# SwitchMatrix.net
KiCad netlist of a schematic drawn in Altium Designer
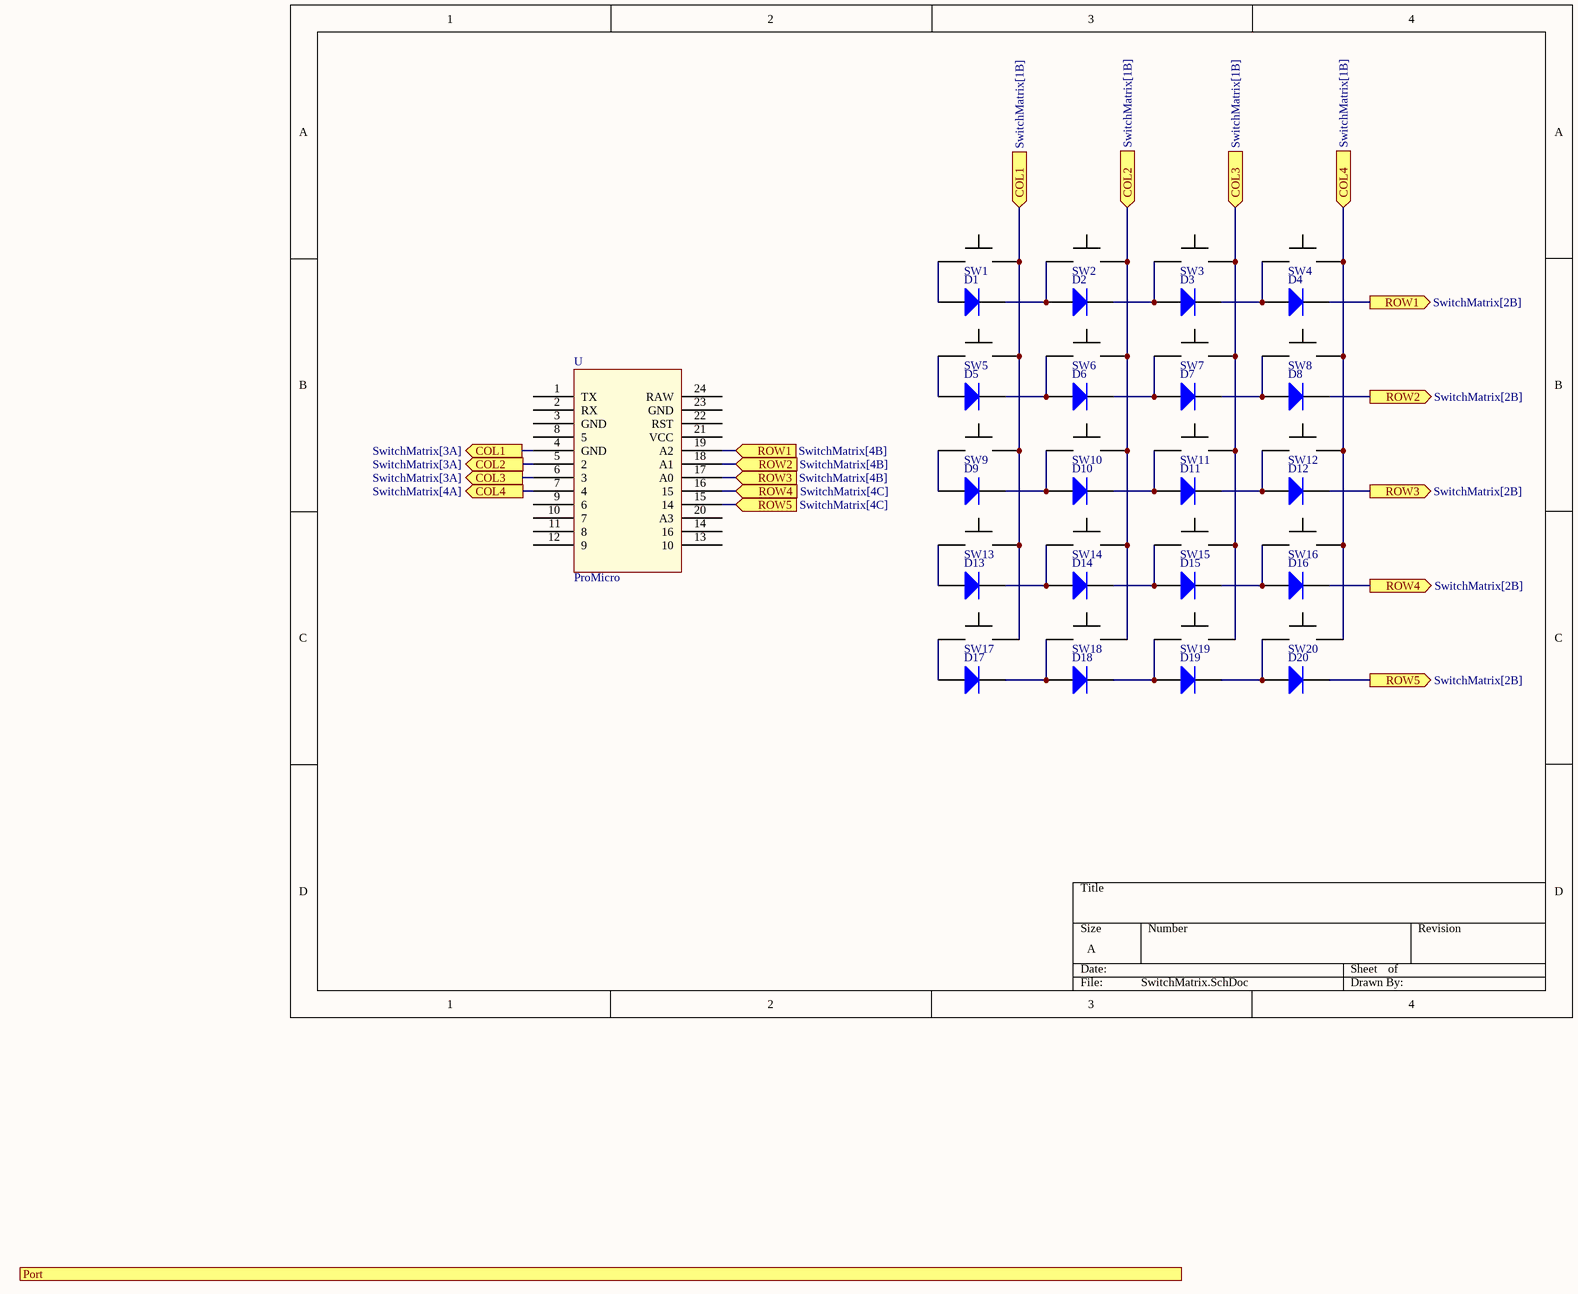
[diagram p0: SwitchMatrix.SchDoc]

(export (version "E")
  (design (tool "Eeschema 10.0.6"))
  (components
    (comp (ref "D1") (value "Diode") (libsource (lib "Simulation Generic Components") (part "Diode")))
    (comp (ref "D2") (value "Diode") (libsource (lib "Simulation Generic Components") (part "Diode")))
    (comp (ref "D3") (value "Diode") (libsource (lib "Simulation Generic Components") (part "Diode")))
    (comp (ref "D4") (value "Diode") (libsource (lib "Simulation Generic Components") (part "Diode")))
    (comp (ref "D5") (value "Diode") (libsource (lib "Simulation Generic Components") (part "Diode")))
    (comp (ref "D6") (value "Diode") (libsource (lib "Simulation Generic Components") (part "Diode")))
    (comp (ref "D7") (value "Diode") (libsource (lib "Simulation Generic Components") (part "Diode")))
    (comp (ref "D8") (value "Diode") (libsource (lib "Simulation Generic Components") (part "Diode")))
    (comp (ref "D9") (value "Diode") (libsource (lib "Simulation Generic Components") (part "Diode")))
    (comp (ref "D10") (value "Diode") (libsource (lib "Simulation Generic Components") (part "Diode")))
    (comp (ref "D11") (value "Diode") (libsource (lib "Simulation Generic Components") (part "Diode")))
    (comp (ref "D12") (value "Diode") (libsource (lib "Simulation Generic Components") (part "Diode")))
    (comp (ref "D13") (value "Diode") (libsource (lib "Simulation Generic Components") (part "Diode")))
    (comp (ref "D14") (value "Diode") (libsource (lib "Simulation Generic Components") (part "Diode")))
    (comp (ref "D15") (value "Diode") (libsource (lib "Simulation Generic Components") (part "Diode")))
    (comp (ref "D16") (value "Diode") (libsource (lib "Simulation Generic Components") (part "Diode")))
    (comp (ref "D17") (value "Diode") (libsource (lib "Simulation Generic Components") (part "Diode")))
    (comp (ref "D18") (value "Diode") (libsource (lib "Simulation Generic Components") (part "Diode")))
    (comp (ref "D19") (value "Diode") (libsource (lib "Simulation Generic Components") (part "Diode")))
    (comp (ref "D20") (value "Diode") (libsource (lib "Simulation Generic Components") (part "Diode")))
    (comp (ref "SW1")
      (value "PG1350 SW")
      (footprint "PG1350")
      (libsource (lib "altium-practice-macropad") (part "PG1350 SW"))
    )
    (comp (ref "SW2")
      (value "PG1350 SW")
      (footprint "PG1350")
      (libsource (lib "altium-practice-macropad") (part "PG1350 SW"))
    )
    (comp (ref "SW3")
      (value "PG1350 SW")
      (footprint "PG1350")
      (libsource (lib "altium-practice-macropad") (part "PG1350 SW"))
    )
    (comp (ref "SW4")
      (value "PG1350 SW")
      (footprint "PG1350")
      (libsource (lib "altium-practice-macropad") (part "PG1350 SW"))
    )
    (comp (ref "SW5")
      (value "PG1350 SW")
      (footprint "PG1350")
      (libsource (lib "altium-practice-macropad") (part "PG1350 SW"))
    )
    (comp (ref "SW6")
      (value "PG1350 SW")
      (footprint "PG1350")
      (libsource (lib "altium-practice-macropad") (part "PG1350 SW"))
    )
    (comp (ref "SW7")
      (value "PG1350 SW")
      (footprint "PG1350")
      (libsource (lib "altium-practice-macropad") (part "PG1350 SW"))
    )
    (comp (ref "SW8")
      (value "PG1350 SW")
      (footprint "PG1350")
      (libsource (lib "altium-practice-macropad") (part "PG1350 SW"))
    )
    (comp (ref "SW9")
      (value "PG1350 SW")
      (footprint "PG1350")
      (libsource (lib "altium-practice-macropad") (part "PG1350 SW"))
    )
    (comp (ref "SW10")
      (value "PG1350 SW")
      (footprint "PG1350")
      (libsource (lib "altium-practice-macropad") (part "PG1350 SW"))
    )
    (comp (ref "SW11")
      (value "PG1350 SW")
      (footprint "PG1350")
      (libsource (lib "altium-practice-macropad") (part "PG1350 SW"))
    )
    (comp (ref "SW12")
      (value "PG1350 SW")
      (footprint "PG1350")
      (libsource (lib "altium-practice-macropad") (part "PG1350 SW"))
    )
    (comp (ref "SW13")
      (value "PG1350 SW")
      (footprint "PG1350")
      (libsource (lib "altium-practice-macropad") (part "PG1350 SW"))
    )
    (comp (ref "SW14")
      (value "PG1350 SW")
      (footprint "PG1350")
      (libsource (lib "altium-practice-macropad") (part "PG1350 SW"))
    )
    (comp (ref "SW15")
      (value "PG1350 SW")
      (footprint "PG1350")
      (libsource (lib "altium-practice-macropad") (part "PG1350 SW"))
    )
    (comp (ref "SW16")
      (value "PG1350 SW")
      (footprint "PG1350")
      (libsource (lib "altium-practice-macropad") (part "PG1350 SW"))
    )
    (comp (ref "SW17")
      (value "PG1350 SW")
      (footprint "PG1350")
      (libsource (lib "altium-practice-macropad") (part "PG1350 SW"))
    )
    (comp (ref "SW18")
      (value "PG1350 SW")
      (footprint "PG1350")
      (libsource (lib "altium-practice-macropad") (part "PG1350 SW"))
    )
    (comp (ref "SW19")
      (value "PG1350 SW")
      (footprint "PG1350")
      (libsource (lib "altium-practice-macropad") (part "PG1350 SW"))
    )
    (comp (ref "SW20")
      (value "PG1350 SW")
      (footprint "PG1350")
      (libsource (lib "altium-practice-macropad") (part "PG1350 SW"))
    )
    (comp (ref "U")
      (value "ProMicro")
      (footprint "ProMicroHeaders")
      (libsource (lib "altium-practice-macropad") (part "ProMicro"))
    )
  )
  (nets
    (net (code "1") (name "/COL1") (class "Default")
      (node (ref "SW1") (pin "2") (pintype "passive"))
      (node (ref "SW13") (pin "2") (pintype "passive"))
      (node (ref "SW17") (pin "2") (pintype "passive"))
      (node (ref "SW5") (pin "2") (pintype "passive"))
      (node (ref "SW9") (pin "2") (pintype "passive"))
      (node (ref "U") (pin "4") (pinfunction "GND_4") (pintype "power_in"))
    )
    (net (code "2") (name "/COL2") (class "Default")
      (node (ref "SW10") (pin "2") (pintype "passive"))
      (node (ref "SW14") (pin "2") (pintype "passive"))
      (node (ref "SW18") (pin "2") (pintype "passive"))
      (node (ref "SW2") (pin "2") (pintype "passive"))
      (node (ref "SW6") (pin "2") (pintype "passive"))
      (node (ref "U") (pin "5") (pinfunction "2_5") (pintype "power_in"))
    )
    (net (code "3") (name "/COL3") (class "Default")
      (node (ref "SW11") (pin "2") (pintype "passive"))
      (node (ref "SW15") (pin "2") (pintype "passive"))
      (node (ref "SW19") (pin "2") (pintype "passive"))
      (node (ref "SW3") (pin "2") (pintype "passive"))
      (node (ref "SW7") (pin "2") (pintype "passive"))
      (node (ref "U") (pin "6") (pinfunction "3_6") (pintype "power_in"))
    )
    (net (code "4") (name "/COL4") (class "Default")
      (node (ref "SW12") (pin "2") (pintype "passive"))
      (node (ref "SW16") (pin "2") (pintype "passive"))
      (node (ref "SW20") (pin "2") (pintype "passive"))
      (node (ref "SW4") (pin "2") (pintype "passive"))
      (node (ref "SW8") (pin "2") (pintype "passive"))
      (node (ref "U") (pin "7") (pinfunction "4_7") (pintype "power_in"))
    )
    (net (code "6") (name "/ROW1") (class "Default")
      (node (ref "D4") (pin "2") (pinfunction "K_2") (pintype "passive"))
      (node (ref "U") (pin "19") (pinfunction "A2_19") (pintype "power_in"))
    )
    (net (code "7") (name "/ROW2") (class "Default")
      (node (ref "D8") (pin "2") (pinfunction "K_2") (pintype "passive"))
      (node (ref "U") (pin "18") (pinfunction "A1_18") (pintype "power_in"))
    )
    (net (code "8") (name "/ROW3") (class "Default")
      (node (ref "D12") (pin "2") (pinfunction "K_2") (pintype "passive"))
      (node (ref "U") (pin "17") (pinfunction "A0_17") (pintype "power_in"))
    )
    (net (code "9") (name "/ROW4") (class "Default")
      (node (ref "D16") (pin "2") (pinfunction "K_2") (pintype "passive"))
      (node (ref "U") (pin "16") (pinfunction "15_16") (pintype "power_in"))
    )
    (net (code "10") (name "/ROW5") (class "Default")
      (node (ref "D20") (pin "2") (pinfunction "K_2") (pintype "passive"))
      (node (ref "U") (pin "15") (pinfunction "14_15") (pintype "power_in"))
    )
    (net (code "11") (name "Net-(D1-A)") (class "Default")
      (node (ref "D1") (pin "1") (pinfunction "A_1") (pintype "passive"))
      (node (ref "SW1") (pin "1") (pintype "passive"))
    )
    (net (code "12") (name "Net-(D1-K)") (class "Default")
      (node (ref "D1") (pin "2") (pinfunction "K_2") (pintype "passive"))
      (node (ref "D2") (pin "1") (pinfunction "A_1") (pintype "passive"))
      (node (ref "SW2") (pin "1") (pintype "passive"))
    )
    (net (code "13") (name "Net-(D2-K)") (class "Default")
      (node (ref "D2") (pin "2") (pinfunction "K_2") (pintype "passive"))
      (node (ref "D3") (pin "1") (pinfunction "A_1") (pintype "passive"))
      (node (ref "SW3") (pin "1") (pintype "passive"))
    )
    (net (code "14") (name "Net-(D3-K)") (class "Default")
      (node (ref "D3") (pin "2") (pinfunction "K_2") (pintype "passive"))
      (node (ref "D4") (pin "1") (pinfunction "A_1") (pintype "passive"))
      (node (ref "SW4") (pin "1") (pintype "passive"))
    )
    (net (code "15") (name "Net-(D5-A)") (class "Default")
      (node (ref "D5") (pin "1") (pinfunction "A_1") (pintype "passive"))
      (node (ref "SW5") (pin "1") (pintype "passive"))
    )
    (net (code "16") (name "Net-(D5-K)") (class "Default")
      (node (ref "D5") (pin "2") (pinfunction "K_2") (pintype "passive"))
      (node (ref "D6") (pin "1") (pinfunction "A_1") (pintype "passive"))
      (node (ref "SW6") (pin "1") (pintype "passive"))
    )
    (net (code "17") (name "Net-(D6-K)") (class "Default")
      (node (ref "D6") (pin "2") (pinfunction "K_2") (pintype "passive"))
      (node (ref "D7") (pin "1") (pinfunction "A_1") (pintype "passive"))
      (node (ref "SW7") (pin "1") (pintype "passive"))
    )
    (net (code "18") (name "Net-(D7-K)") (class "Default")
      (node (ref "D7") (pin "2") (pinfunction "K_2") (pintype "passive"))
      (node (ref "D8") (pin "1") (pinfunction "A_1") (pintype "passive"))
      (node (ref "SW8") (pin "1") (pintype "passive"))
    )
    (net (code "19") (name "Net-(D9-A)") (class "Default")
      (node (ref "D9") (pin "1") (pinfunction "A_1") (pintype "passive"))
      (node (ref "SW9") (pin "1") (pintype "passive"))
    )
    (net (code "20") (name "Net-(D10-A)") (class "Default")
      (node (ref "D10") (pin "1") (pinfunction "A_1") (pintype "passive"))
      (node (ref "D9") (pin "2") (pinfunction "K_2") (pintype "passive"))
      (node (ref "SW10") (pin "1") (pintype "passive"))
    )
    (net (code "21") (name "Net-(D10-K)") (class "Default")
      (node (ref "D10") (pin "2") (pinfunction "K_2") (pintype "passive"))
      (node (ref "D11") (pin "1") (pinfunction "A_1") (pintype "passive"))
      (node (ref "SW11") (pin "1") (pintype "passive"))
    )
    (net (code "22") (name "Net-(D11-K)") (class "Default")
      (node (ref "D11") (pin "2") (pinfunction "K_2") (pintype "passive"))
      (node (ref "D12") (pin "1") (pinfunction "A_1") (pintype "passive"))
      (node (ref "SW12") (pin "1") (pintype "passive"))
    )
    (net (code "23") (name "Net-(D13-A)") (class "Default")
      (node (ref "D13") (pin "1") (pinfunction "A_1") (pintype "passive"))
      (node (ref "SW13") (pin "1") (pintype "passive"))
    )
    (net (code "24") (name "Net-(D13-K)") (class "Default")
      (node (ref "D13") (pin "2") (pinfunction "K_2") (pintype "passive"))
      (node (ref "D14") (pin "1") (pinfunction "A_1") (pintype "passive"))
      (node (ref "SW14") (pin "1") (pintype "passive"))
    )
    (net (code "25") (name "Net-(D14-K)") (class "Default")
      (node (ref "D14") (pin "2") (pinfunction "K_2") (pintype "passive"))
      (node (ref "D15") (pin "1") (pinfunction "A_1") (pintype "passive"))
      (node (ref "SW15") (pin "1") (pintype "passive"))
    )
    (net (code "26") (name "Net-(D15-K)") (class "Default")
      (node (ref "D15") (pin "2") (pinfunction "K_2") (pintype "passive"))
      (node (ref "D16") (pin "1") (pinfunction "A_1") (pintype "passive"))
      (node (ref "SW16") (pin "1") (pintype "passive"))
    )
    (net (code "27") (name "Net-(D17-A)") (class "Default")
      (node (ref "D17") (pin "1") (pinfunction "A_1") (pintype "passive"))
      (node (ref "SW17") (pin "1") (pintype "passive"))
    )
    (net (code "28") (name "Net-(D17-K)") (class "Default")
      (node (ref "D17") (pin "2") (pinfunction "K_2") (pintype "passive"))
      (node (ref "D18") (pin "1") (pinfunction "A_1") (pintype "passive"))
      (node (ref "SW18") (pin "1") (pintype "passive"))
    )
    (net (code "29") (name "Net-(D18-K)") (class "Default")
      (node (ref "D18") (pin "2") (pinfunction "K_2") (pintype "passive"))
      (node (ref "D19") (pin "1") (pinfunction "A_1") (pintype "passive"))
      (node (ref "SW19") (pin "1") (pintype "passive"))
    )
    (net (code "30") (name "Net-(D19-K)") (class "Default")
      (node (ref "D19") (pin "2") (pinfunction "K_2") (pintype "passive"))
      (node (ref "D20") (pin "1") (pinfunction "A_1") (pintype "passive"))
      (node (ref "SW20") (pin "1") (pintype "passive"))
    )
    (net (code "31") (name "unconnected-(U-5-Pad8)") (class "Default")
      (node (ref "U") (pin "8") (pinfunction "5_8") (pintype "power_in"))
    )
    (net (code "32") (name "unconnected-(U-6-Pad9)") (class "Default")
      (node (ref "U") (pin "9") (pinfunction "6_9") (pintype "power_in"))
    )
    (net (code "33") (name "unconnected-(U-7-Pad10)") (class "Default")
      (node (ref "U") (pin "10") (pinfunction "7_10") (pintype "power_in"))
    )
    (net (code "34") (name "unconnected-(U-8-Pad11)") (class "Default")
      (node (ref "U") (pin "11") (pinfunction "8_11") (pintype "power_in"))
    )
    (net (code "35") (name "unconnected-(U-9-Pad12)") (class "Default")
      (node (ref "U") (pin "12") (pinfunction "9_12") (pintype "power_in"))
    )
    (net (code "36") (name "unconnected-(U-10-Pad13)") (class "Default")
      (node (ref "U") (pin "13") (pinfunction "10_13") (pintype "power_in"))
    )
    (net (code "37") (name "unconnected-(U-16-Pad14)") (class "Default")
      (node (ref "U") (pin "14") (pinfunction "16_14") (pintype "power_in"))
    )
    (net (code "38") (name "unconnected-(U-A3-Pad20)") (class "Default")
      (node (ref "U") (pin "20") (pinfunction "A3_20") (pintype "power_in"))
    )
    (net (code "39") (name "unconnected-(U-GND-Pad3)") (class "Default")
      (node (ref "U") (pin "3") (pinfunction "GND_3") (pintype "power_in"))
    )
    (net (code "40") (name "unconnected-(U-GND-Pad23)") (class "Default")
      (node (ref "U") (pin "23") (pinfunction "GND_23") (pintype "power_in"))
    )
    (net (code "41") (name "unconnected-(U-RAW-Pad24)") (class "Default")
      (node (ref "U") (pin "24") (pinfunction "RAW_24") (pintype "power_in"))
    )
    (net (code "42") (name "unconnected-(U-RST-Pad22)") (class "Default")
      (node (ref "U") (pin "22") (pinfunction "RST_22") (pintype "power_in"))
    )
    (net (code "43") (name "unconnected-(U-RX-Pad2)") (class "Default")
      (node (ref "U") (pin "2") (pinfunction "RX_2") (pintype "power_in"))
    )
    (net (code "44") (name "unconnected-(U-TX-Pad1)") (class "Default")
      (node (ref "U") (pin "1") (pinfunction "TX_1") (pintype "power_in"))
    )
    (net (code "45") (name "unconnected-(U-VCC-Pad21)") (class "Default")
      (node (ref "U") (pin "21") (pinfunction "VCC_21") (pintype "power_in"))
    )
  )
)
